# 3_3.net
KiCad netlist of a schematic drawn in Altium Designer
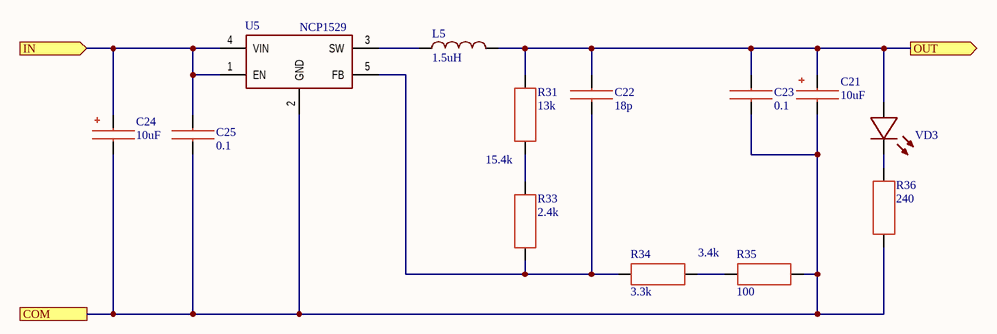
[diagram p0: 3_3.SchDoc]

(export (version "E")
  (design (tool "Eeschema 10.0.6"))
  (components
    (comp (ref "C21")
      (value "10uF")
      (footprint "Tantal Type C")
      (description "16 V")
      (libsource (lib "Capacitor") (part "Tantal C 10uF"))
    )
    (comp (ref "C22")
      (value "18p")
      (footprint "Capacitor:CC0805_3D")
      (libsource (lib "Capacitor") (part "CC0805 X uF"))
    )
    (comp (ref "C23")
      (value "0.1")
      (footprint "Capacitor:CC0805_3D")
      (libsource (lib "Capacitor") (part "CC0805 X uF"))
    )
    (comp (ref "C24")
      (value "10uF")
      (footprint "Tantal Type C")
      (description "16 V")
      (libsource (lib "Capacitor") (part "Tantal C 10uF"))
    )
    (comp (ref "C25")
      (value "0.1")
      (footprint "Capacitor:CC0805_3D")
      (libsource (lib "Capacitor") (part "CC0805 X uF"))
    )
    (comp (ref "L5")
      (value "4700uH")
      (footprint "SDR0805:SDR0805")
      (libsource (lib "SDR0805") (part "SDR0805"))
    )
    (comp (ref "R31")
      (value "13k")
      (footprint "Resistor:RC0805_3D")
      (libsource (lib "Resistor") (part "RC0805 X Ohm"))
    )
    (comp (ref "R33")
      (value "2.4k")
      (footprint "Resistor:RC0805_3D")
      (libsource (lib "Resistor") (part "RC0805 X Ohm"))
    )
    (comp (ref "R34")
      (value "3.3k")
      (footprint "Resistor:RC0805_3D")
      (libsource (lib "Resistor") (part "RC0805 X Ohm"))
    )
    (comp (ref "R35")
      (value "100")
      (footprint "Resistor:RC0805_3D")
      (libsource (lib "Resistor") (part "RC0805 X Ohm"))
    )
    (comp (ref "R36")
      (value "240")
      (footprint "Resistor:RC0805_3D")
      (libsource (lib "Resistor") (part "RC0805 X Ohm"))
    )
    (comp (ref "U5") (value "NCP1529") (footprint "TSOP5") (libsource (lib "NCP1529") (part "NCP1529")))
    (comp (ref "VD3")
      (value "Value")
      (footprint "KA-3021SGCT:2030")
      (libsource (lib "KA-3021SGCT") (part "KA-3021SGCT"))
    )
  )
  (nets
    (net (code "1") (name "/COM") (class "Default")
      (node (ref "C21") (pin "1") (pinfunction "1_1") (pintype "passive"))
      (node (ref "C23") (pin "1") (pinfunction "1_1") (pintype "passive"))
      (node (ref "C24") (pin "1") (pinfunction "1_1") (pintype "passive"))
      (node (ref "C25") (pin "1") (pinfunction "1_1") (pintype "passive"))
      (node (ref "R35") (pin "2") (pinfunction "2_2") (pintype "passive"))
      (node (ref "R36") (pin "1") (pinfunction "1_1") (pintype "passive"))
      (node (ref "U5") (pin "2") (pinfunction "GND_2") (pintype "passive"))
    )
    (net (code "2") (name "/IN") (class "Default")
      (node (ref "C24") (pin "2") (pinfunction "2_2") (pintype "passive"))
      (node (ref "C25") (pin "2") (pinfunction "2_2") (pintype "passive"))
      (node (ref "U5") (pin "1") (pinfunction "EN_1") (pintype "passive"))
      (node (ref "U5") (pin "4") (pinfunction "VIN_4") (pintype "passive"))
    )
    (net (code "3") (name "/OUT") (class "Default")
      (node (ref "C21") (pin "2") (pinfunction "2_2") (pintype "passive"))
      (node (ref "C22") (pin "2") (pinfunction "2_2") (pintype "passive"))
      (node (ref "C23") (pin "2") (pinfunction "2_2") (pintype "passive"))
      (node (ref "L5") (pin "2") (pinfunction "2_2") (pintype "passive"))
      (node (ref "R31") (pin "2") (pinfunction "2_2") (pintype "passive"))
      (node (ref "VD3") (pin "2") (pinfunction "2_2") (pintype "passive"))
    )
    (net (code "4") (name "Net-(R31-Pad1)") (class "Default")
      (node (ref "R31") (pin "1") (pinfunction "1_1") (pintype "passive"))
      (node (ref "R33") (pin "2") (pinfunction "2_2") (pintype "passive"))
    )
    (net (code "5") (name "Net-(R34-Pad2)") (class "Default")
      (node (ref "R34") (pin "2") (pinfunction "2_2") (pintype "passive"))
      (node (ref "R35") (pin "1") (pinfunction "1_1") (pintype "passive"))
    )
    (net (code "6") (name "Net-(R36-Pad2)") (class "Default")
      (node (ref "R36") (pin "2") (pinfunction "2_2") (pintype "passive"))
      (node (ref "VD3") (pin "1") (pinfunction "1_1") (pintype "passive"))
    )
    (net (code "7") (name "Net-(U5-FB)") (class "Default")
      (node (ref "C22") (pin "1") (pinfunction "1_1") (pintype "passive"))
      (node (ref "R33") (pin "1") (pinfunction "1_1") (pintype "passive"))
      (node (ref "R34") (pin "1") (pinfunction "1_1") (pintype "passive"))
      (node (ref "U5") (pin "5") (pinfunction "FB_5") (pintype "passive"))
    )
    (net (code "8") (name "Net-(U5-SW)") (class "Default")
      (node (ref "L5") (pin "1") (pinfunction "1_1") (pintype "passive"))
      (node (ref "U5") (pin "3") (pinfunction "SW_3") (pintype "passive"))
    )
  )
)
